# Timebase_shcematics.net
KiCad netlist of a schematic drawn in Altium Designer
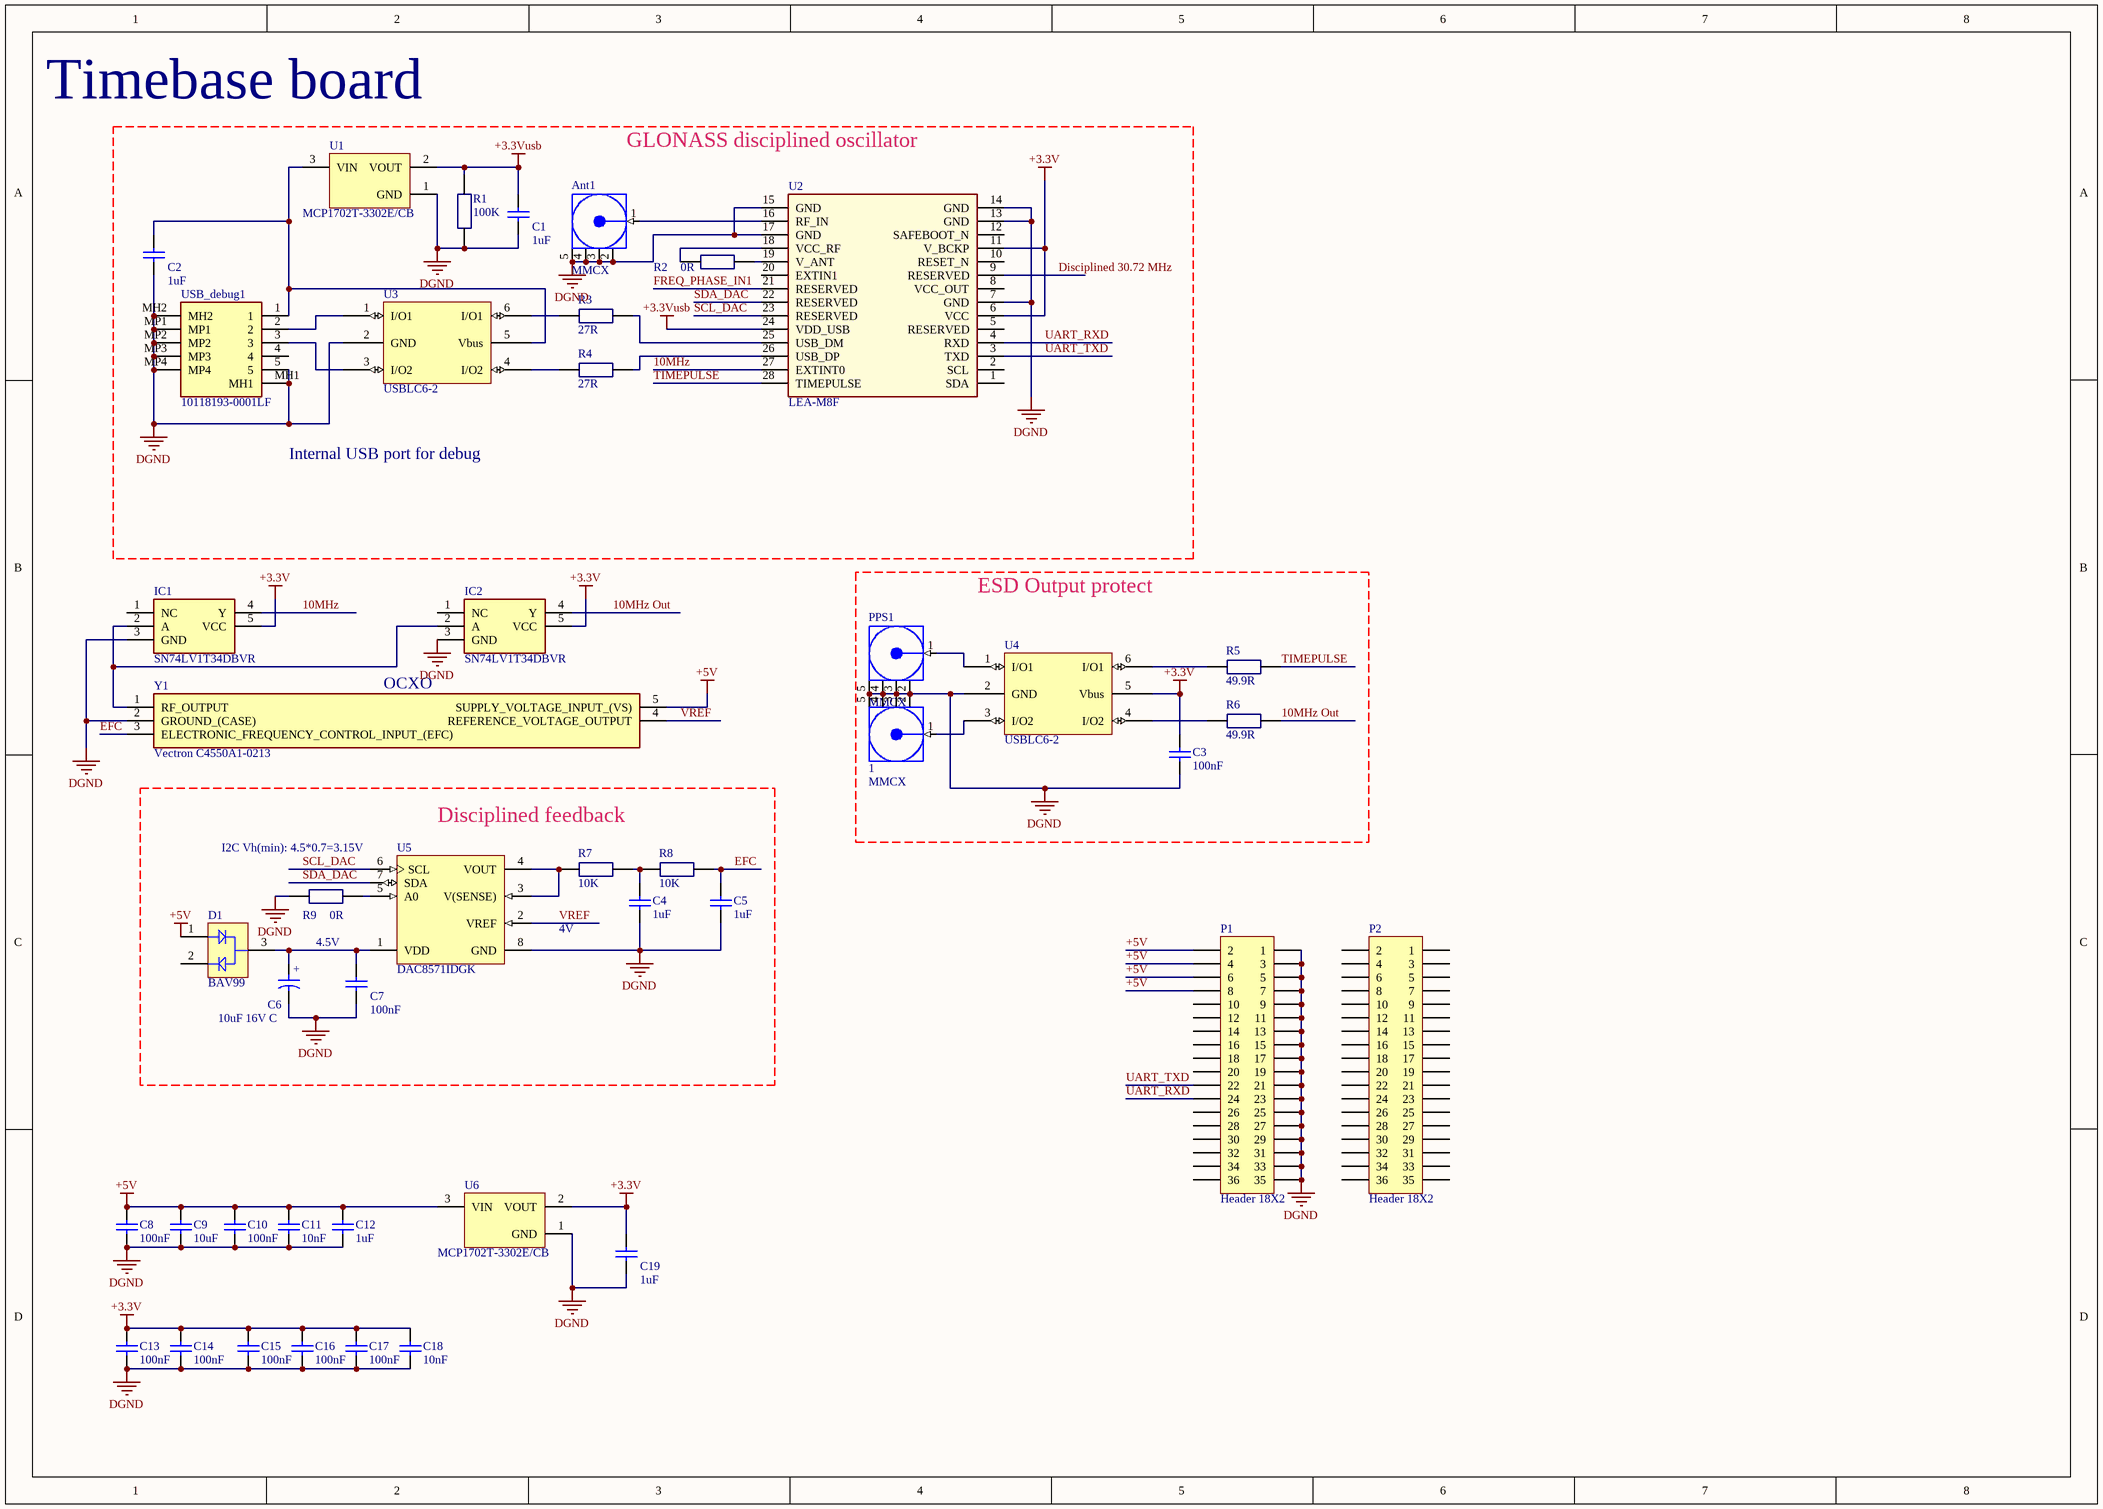
[diagram p0: Timebase_shcematics.SchDoc]

(export (version "E")
  (design (tool "Eeschema 10.0.6"))
  (components
    (comp (ref "1")
      (value "MMCX")
      (footprint "MMCX2.54-V5")
      (description "RF Coaxial PCB Connector, MMCX; Thru-Hole, Vertical Mount Plug,  50 Ohm Impedance")
      (fields (field (name "PUBLISHER") "Altium Limited"))
      (libsource (lib "Miscellaneous Connectors") (part "COAX-M"))
    )
    (comp (ref "Ant1")
      (value "MMCX")
      (footprint "MMCX2.54-V5")
      (description "RF Coaxial PCB Connector, MMCX; Thru-Hole, Vertical Mount Plug,  50 Ohm Impedance")
      (fields (field (name "PUBLISHER") "Altium Limited"))
      (libsource (lib "Miscellaneous Connectors") (part "COAX-M"))
    )
    (comp (ref "C1")
      (value "1uF")
      (footprint "CAP 0603")
      (description "Capacitor (Semiconductor SIM Model)")
      (fields (field (name "PUBLISHER") "Altium Limited"))
      (libsource (lib "Miscellaneous Devices") (part "Cap Semi"))
    )
    (comp (ref "C2")
      (value "1uF")
      (footprint "CAP 0603")
      (description "Capacitor (Semiconductor SIM Model)")
      (fields (field (name "PUBLISHER") "Altium Limited"))
      (libsource (lib "Miscellaneous Devices") (part "Cap Semi"))
    )
    (comp (ref "C3")
      (value "100nF")
      (footprint "CAP 0603")
      (description "Capacitor (Semiconductor SIM Model)")
      (fields (field (name "PUBLISHER") "Altium Limited"))
      (libsource (lib "Miscellaneous Devices") (part "Cap Semi"))
    )
    (comp (ref "C4")
      (value "1uF")
      (footprint "CAP 0603")
      (description "Capacitor (Semiconductor SIM Model)")
      (fields (field (name "PUBLISHER") "Altium Limited"))
      (libsource (lib "Miscellaneous Devices") (part "Cap Semi"))
    )
    (comp (ref "C5")
      (value "1uF")
      (footprint "CAP 0603")
      (description "Capacitor (Semiconductor SIM Model)")
      (fields (field (name "PUBLISHER") "Altium Limited"))
      (libsource (lib "Miscellaneous Devices") (part "Cap Semi"))
    )
    (comp (ref "C6")
      (value "10uF 16V C")
      (footprint "CAPMP6032X280N")
      (description "Polarised capacitor")
      (fields
        (field (name "PART NUMBER") "CTE6032-28_10UF_25V_10%_LESR0500")
        (field (name "VOLTAGE") "25V")
        (field (name "AUTHOR") "CERN DEM JLC")
      )
      (libsource (lib "Capacitors") (part "Capacitor - polarized"))
    )
    (comp (ref "C7")
      (value "100nF")
      (footprint "CAP 0603")
      (description "Capacitor (Semiconductor SIM Model)")
      (fields (field (name "PUBLISHER") "Altium Limited"))
      (libsource (lib "Miscellaneous Devices") (part "Cap Semi"))
    )
    (comp (ref "C8")
      (value "100nF")
      (footprint "CAP 0603")
      (description "Capacitor (Semiconductor SIM Model)")
      (fields (field (name "PUBLISHER") "Altium Limited"))
      (libsource (lib "Miscellaneous Devices") (part "Cap Semi"))
    )
    (comp (ref "C9")
      (value "10uF")
      (footprint "CAP 0603")
      (description "Capacitor (Semiconductor SIM Model)")
      (fields (field (name "PUBLISHER") "Altium Limited"))
      (libsource (lib "Miscellaneous Devices") (part "Cap Semi"))
    )
    (comp (ref "C10")
      (value "100nF")
      (footprint "CAP 0603")
      (description "Capacitor (Semiconductor SIM Model)")
      (fields (field (name "PUBLISHER") "Altium Limited"))
      (libsource (lib "Miscellaneous Devices") (part "Cap Semi"))
    )
    (comp (ref "C11")
      (value "10nF")
      (footprint "CAP 0603")
      (description "Capacitor (Semiconductor SIM Model)")
      (fields (field (name "PUBLISHER") "Altium Limited"))
      (libsource (lib "Miscellaneous Devices") (part "Cap Semi"))
    )
    (comp (ref "C12")
      (value "1uF")
      (footprint "CAP 0603")
      (description "Capacitor (Semiconductor SIM Model)")
      (fields (field (name "PUBLISHER") "Altium Limited"))
      (libsource (lib "Miscellaneous Devices") (part "Cap Semi"))
    )
    (comp (ref "C13")
      (value "100nF")
      (footprint "CAP 0603")
      (description "Capacitor (Semiconductor SIM Model)")
      (fields (field (name "PUBLISHER") "Altium Limited"))
      (libsource (lib "Miscellaneous Devices") (part "Cap Semi"))
    )
    (comp (ref "C14")
      (value "100nF")
      (footprint "CAP 0603")
      (description "Capacitor (Semiconductor SIM Model)")
      (fields (field (name "PUBLISHER") "Altium Limited"))
      (libsource (lib "Miscellaneous Devices") (part "Cap Semi"))
    )
    (comp (ref "C15")
      (value "100nF")
      (footprint "CAP 0603")
      (description "Capacitor (Semiconductor SIM Model)")
      (fields (field (name "PUBLISHER") "Altium Limited"))
      (libsource (lib "Miscellaneous Devices") (part "Cap Semi"))
    )
    (comp (ref "C16")
      (value "100nF")
      (footprint "CAP 0603")
      (description "Capacitor (Semiconductor SIM Model)")
      (fields (field (name "PUBLISHER") "Altium Limited"))
      (libsource (lib "Miscellaneous Devices") (part "Cap Semi"))
    )
    (comp (ref "C17")
      (value "100nF")
      (footprint "CAP 0603")
      (description "Capacitor (Semiconductor SIM Model)")
      (fields (field (name "PUBLISHER") "Altium Limited"))
      (libsource (lib "Miscellaneous Devices") (part "Cap Semi"))
    )
    (comp (ref "C18")
      (value "10nF")
      (footprint "CAP 0603")
      (description "Capacitor (Semiconductor SIM Model)")
      (fields (field (name "PUBLISHER") "Altium Limited"))
      (libsource (lib "Miscellaneous Devices") (part "Cap Semi"))
    )
    (comp (ref "C19")
      (value "1uF")
      (footprint "CAP 0603")
      (description "Capacitor (Semiconductor SIM Model)")
      (fields (field (name "PUBLISHER") "Altium Limited"))
      (libsource (lib "Miscellaneous Devices") (part "Cap Semi"))
    )
    (comp (ref "D1")
      (value "BAV99")
      (footprint "INF-SOT23_N")
      (description "Silicon Switching Diode, SOT23, Reel, Green")
      (fields (field (name "MANUFACTURER") "Infineon"))
      (libsource (lib "Infineon_Transistor_&_Diode") (part "BAV99"))
    )
    (comp (ref "IC1")
      (value "SN74LV1T34DBVR")
      (footprint "SamacSys:SOT95P280X145-5N")
      (description "Integrated Circuit")
      (fields (field (name "MOUSER PART NUMBER") "595-SN74LV1T34DBVR"))
      (libsource (lib "*") (part "SN74LV1T34DBVR"))
    )
    (comp (ref "IC2")
      (value "SN74LV1T34DBVR")
      (footprint "SamacSys:SOT95P280X145-5N")
      (description "Integrated Circuit")
      (fields (field (name "MOUSER PART NUMBER") "595-SN74LV1T34DBVR"))
      (libsource (lib "*") (part "SN74LV1T34DBVR"))
    )
    (comp (ref "P1")
      (value "Header 18X2")
      (footprint "HDR2X18")
      (description "Header, 18-Pin, Dual row")
      (fields (field (name "PUBLISHER") "Altium Limited"))
      (libsource (lib "Miscellaneous Connectors") (part "Header 18X2"))
    )
    (comp (ref "P2")
      (value "Header 18X2")
      (footprint "HDR2X18")
      (description "Header, 18-Pin, Dual row")
      (fields (field (name "PUBLISHER") "Altium Limited"))
      (libsource (lib "Miscellaneous Connectors") (part "Header 18X2"))
    )
    (comp (ref "PPS1")
      (value "MMCX")
      (footprint "MMCX2.54-V5")
      (description "RF Coaxial PCB Connector, MMCX; Thru-Hole, Vertical Mount Plug,  50 Ohm Impedance")
      (fields (field (name "PUBLISHER") "Altium Limited"))
      (libsource (lib "Miscellaneous Connectors") (part "COAX-M"))
    )
    (comp (ref "R1")
      (value "100K")
      (footprint "1608[0603]")
      (libsource (lib "Микрон-3") (part "Resistor 0805"))
    )
    (comp (ref "R2")
      (value "0R")
      (footprint "1608[0603]")
      (libsource (lib "Микрон-3") (part "Resistor 0805"))
    )
    (comp (ref "R3")
      (value "27R")
      (footprint "1608[0603]")
      (libsource (lib "Микрон-3") (part "Resistor 0805"))
    )
    (comp (ref "R4")
      (value "27R")
      (footprint "1608[0603]")
      (libsource (lib "Микрон-3") (part "Resistor 0805"))
    )
    (comp (ref "R5")
      (value "49.9R")
      (footprint "1608[0603]")
      (libsource (lib "Микрон-3") (part "Resistor 0805"))
    )
    (comp (ref "R6")
      (value "49.9R")
      (footprint "1608[0603]")
      (libsource (lib "Микрон-3") (part "Resistor 0805"))
    )
    (comp (ref "R7")
      (value "10K")
      (footprint "1608[0603]")
      (libsource (lib "Микрон-3") (part "Resistor 0805"))
    )
    (comp (ref "R8")
      (value "10K")
      (footprint "1608[0603]")
      (libsource (lib "Микрон-3") (part "Resistor 0805"))
    )
    (comp (ref "R9")
      (value "0R")
      (footprint "1608[0603]")
      (libsource (lib "Микрон-3") (part "Resistor 0805"))
    )
    (comp (ref "U1")
      (value "MCP1702T-3302E/CB")
      (footprint "SOT-23A-CB3_N")
      (description "250 mA Low Quiescent Current LDO Regulator, 3-Pin SOT-23A, Extended Temperature, Tape and Reel")
      (fields (field (name "PUBLISHER") "Altium Limited"))
      (libsource (lib "Microchip Power Mgt Line Regulator") (part "MCP1702T-3302E/CB"))
    )
    (comp (ref "U2")
      (value "LEA-M8F")
      (footprint "LEA")
      (description "u-blox LEA GNSS module")
      (fields (field (name "MANUFACTURER") "u-blox"))
      (libsource (lib "ubloxLib") (part "LEA"))
    )
    (comp (ref "U3") (value "USBLC6-2") (footprint "SOT23-6L") (libsource (lib "Микрон-3") (part "USBLC6-2")))
    (comp (ref "U4") (value "USBLC6-2") (footprint "SOT23-6L") (libsource (lib "Микрон-3") (part "USBLC6-2")))
    (comp (ref "U5")
      (value "DAC8571IDGK")
      (footprint "TI-DGK8_N")
      (fields (field (name "MANUFACTURER") "Texas Instruments"))
      (libsource (lib "TI Data Converters Digital to Analog Converter") (part "DAC8571IDGK"))
    )
    (comp (ref "U6")
      (value "MCP1702T-3302E/CB")
      (footprint "SOT-23A-CB3_N")
      (description "250 mA Low Quiescent Current LDO Regulator, 3-Pin SOT-23A, Extended Temperature, Tape and Reel")
      (fields (field (name "PUBLISHER") "Altium Limited"))
      (libsource (lib "Microchip Power Mgt Line Regulator") (part "MCP1702T-3302E/CB"))
    )
    (comp (ref "USB_debug1")
      (value "10118193-0001LF")
      (footprint "SamacSys:101181930001LF")
      (description "Connector")
      (fields (field (name "MOUSER PART NUMBER") "649-10118193-0001LF"))
      (libsource (lib "*") (part "10118193-0001LF"))
    )
    (comp (ref "Y1")
      (value "Vectron C4550A1-0213")
      (footprint "SamacSys:C4550C508SV120RFSA11128MHZ")
      (description "Crystal or Oscillator")
      (libsource (lib "SamacSys") (part "C4550C508SV120RFSA1112.8MHZ"))
    )
  )
  (nets
    (net (code "1") (name "+3.3V") (class "Default")
      (node (ref "C13") (pin "2") (pinfunction "2_2") (pintype "passive"))
      (node (ref "C14") (pin "2") (pinfunction "2_2") (pintype "passive"))
      (node (ref "C15") (pin "2") (pinfunction "2_2") (pintype "passive"))
      (node (ref "C16") (pin "2") (pinfunction "2_2") (pintype "passive"))
      (node (ref "C17") (pin "2") (pinfunction "2_2") (pintype "passive"))
      (node (ref "C18") (pin "2") (pinfunction "2_2") (pintype "passive"))
      (node (ref "C19") (pin "2") (pinfunction "2_2") (pintype "passive"))
      (node (ref "C3") (pin "2") (pinfunction "2_2") (pintype "passive"))
      (node (ref "IC1") (pin "5") (pinfunction "VCC_5") (pintype "passive"))
      (node (ref "IC2") (pin "5") (pinfunction "VCC_5") (pintype "passive"))
      (node (ref "U2") (pin "11") (pinfunction "V_BCKP_11") (pintype "passive"))
      (node (ref "U2") (pin "6") (pinfunction "VCC_6") (pintype "passive"))
      (node (ref "U4") (pin "5") (pinfunction "Vbus_5") (pintype "power_in"))
      (node (ref "U6") (pin "2") (pinfunction "VOUT_2") (pintype "power_in"))
    )
    (net (code "2") (name "+3.3Vusb") (class "Default")
      (node (ref "C1") (pin "2") (pinfunction "2_2") (pintype "passive"))
      (node (ref "R1") (pin "1") (pinfunction "A_1") (pintype "passive"))
      (node (ref "U1") (pin "2") (pinfunction "VOUT_2") (pintype "power_in"))
      (node (ref "U2") (pin "24") (pinfunction "VDD_USB_24") (pintype "passive"))
    )
    (net (code "3") (name "+5V") (class "Default")
      (node (ref "C10") (pin "2") (pinfunction "2_2") (pintype "passive"))
      (node (ref "C11") (pin "2") (pinfunction "2_2") (pintype "passive"))
      (node (ref "C12") (pin "2") (pinfunction "2_2") (pintype "passive"))
      (node (ref "C8") (pin "2") (pinfunction "2_2") (pintype "passive"))
      (node (ref "C9") (pin "2") (pinfunction "2_2") (pintype "passive"))
      (node (ref "D1") (pin "1") (pinfunction "A1_1") (pintype "passive"))
      (node (ref "P1") (pin "2") (pinfunction "2_2") (pintype "passive"))
      (node (ref "P1") (pin "4") (pinfunction "4_4") (pintype "passive"))
      (node (ref "P1") (pin "6") (pinfunction "6_6") (pintype "passive"))
      (node (ref "P1") (pin "8") (pinfunction "8_8") (pintype "passive"))
      (node (ref "U6") (pin "3") (pinfunction "VIN_3") (pintype "power_in"))
      (node (ref "Y1") (pin "5") (pinfunction "SUPPLY_VOLTAGE_INPUT_(VS)_5") (pintype "passive"))
    )
    (net (code "4") (name "/10MHz") (class "Default")
      (node (ref "IC1") (pin "4") (pinfunction "Y_4") (pintype "passive"))
      (node (ref "U2") (pin "27") (pinfunction "EXTINT0_27") (pintype "passive"))
    )
    (net (code "5") (name "/10MHz Out") (class "Default")
      (node (ref "IC2") (pin "4") (pinfunction "Y_4") (pintype "passive"))
      (node (ref "R6") (pin "1") (pinfunction "A_1") (pintype "passive"))
    )
    (net (code "6") (name "/Disciplined 30.72 MHz") (class "Default")
      (node (ref "U2") (pin "9") (pinfunction "RESERVED_9") (pintype "passive"))
    )
    (net (code "7") (name "/EFC") (class "Default")
      (node (ref "C5") (pin "2") (pinfunction "2_2") (pintype "passive"))
      (node (ref "R8") (pin "1") (pinfunction "A_1") (pintype "passive"))
      (node (ref "Y1") (pin "3") (pinfunction "ELECTRONIC_FREQUENCY_CONTROL_INPUT_(EFC)_3") (pintype "passive"))
    )
    (net (code "8") (name "/FREQ_PHASE_IN1") (class "Default")
      (node (ref "U2") (pin "21") (pinfunction "RESERVED_21") (pintype "passive"))
    )
    (net (code "9") (name "/SCL_DAC") (class "Default")
      (node (ref "U2") (pin "23") (pinfunction "RESERVED_23") (pintype "passive"))
      (node (ref "U5") (pin "6") (pinfunction "SCL_6") (pintype "input"))
    )
    (net (code "10") (name "/SDA_DAC") (class "Default")
      (node (ref "U2") (pin "22") (pinfunction "RESERVED_22") (pintype "passive"))
      (node (ref "U5") (pin "7") (pinfunction "SDA_7") (pintype "bidirectional"))
    )
    (net (code "11") (name "/TIMEPULSE") (class "Default")
      (node (ref "R5") (pin "1") (pinfunction "A_1") (pintype "passive"))
      (node (ref "U2") (pin "28") (pinfunction "TIMEPULSE_28") (pintype "passive"))
    )
    (net (code "12") (name "/UART_RXD") (class "Default")
      (node (ref "P1") (pin "24") (pinfunction "24_24") (pintype "passive"))
      (node (ref "U2") (pin "4") (pinfunction "RXD_4") (pintype "passive"))
    )
    (net (code "13") (name "/UART_TXD") (class "Default")
      (node (ref "P1") (pin "22") (pinfunction "22_22") (pintype "passive"))
      (node (ref "U2") (pin "3") (pinfunction "TXD_3") (pintype "passive"))
    )
    (net (code "14") (name "/VREF") (class "Default")
      (node (ref "U5") (pin "2") (pinfunction "VREF_2") (pintype "input"))
      (node (ref "Y1") (pin "4") (pinfunction "REFERENCE_VOLTAGE_OUTPUT_4") (pintype "passive"))
    )
    (net (code "15") (name "DGND") (class "Default")
      (node (ref "1") (pin "2") (pinfunction "GND_2") (pintype "power_in"))
      (node (ref "1") (pin "3") (pinfunction "GND_3") (pintype "power_in"))
      (node (ref "1") (pin "4") (pinfunction "GND_4") (pintype "power_in"))
      (node (ref "1") (pin "5") (pinfunction "GND_5") (pintype "power_in"))
      (node (ref "Ant1") (pin "2") (pinfunction "GND_2") (pintype "power_in"))
      (node (ref "Ant1") (pin "3") (pinfunction "GND_3") (pintype "power_in"))
      (node (ref "Ant1") (pin "4") (pinfunction "GND_4") (pintype "power_in"))
      (node (ref "Ant1") (pin "5") (pinfunction "GND_5") (pintype "power_in"))
      (node (ref "C1") (pin "1") (pinfunction "1_1") (pintype "passive"))
      (node (ref "C10") (pin "1") (pinfunction "1_1") (pintype "passive"))
      (node (ref "C11") (pin "1") (pinfunction "1_1") (pintype "passive"))
      (node (ref "C12") (pin "1") (pinfunction "1_1") (pintype "passive"))
      (node (ref "C13") (pin "1") (pinfunction "1_1") (pintype "passive"))
      (node (ref "C14") (pin "1") (pinfunction "1_1") (pintype "passive"))
      (node (ref "C15") (pin "1") (pinfunction "1_1") (pintype "passive"))
      (node (ref "C16") (pin "1") (pinfunction "1_1") (pintype "passive"))
      (node (ref "C17") (pin "1") (pinfunction "1_1") (pintype "passive"))
      (node (ref "C18") (pin "1") (pinfunction "1_1") (pintype "passive"))
      (node (ref "C19") (pin "1") (pinfunction "1_1") (pintype "passive"))
      (node (ref "C2") (pin "1") (pinfunction "1_1") (pintype "passive"))
      (node (ref "C3") (pin "1") (pinfunction "1_1") (pintype "passive"))
      (node (ref "C4") (pin "1") (pinfunction "1_1") (pintype "passive"))
      (node (ref "C5") (pin "1") (pinfunction "1_1") (pintype "passive"))
      (node (ref "C6") (pin "2") (pinfunction "2_2") (pintype "passive"))
      (node (ref "C7") (pin "1") (pinfunction "1_1") (pintype "passive"))
      (node (ref "C8") (pin "1") (pinfunction "1_1") (pintype "passive"))
      (node (ref "C9") (pin "1") (pinfunction "1_1") (pintype "passive"))
      (node (ref "IC1") (pin "3") (pinfunction "GND_3") (pintype "passive"))
      (node (ref "IC2") (pin "3") (pinfunction "GND_3") (pintype "passive"))
      (node (ref "P1") (pin "1") (pinfunction "1_1") (pintype "passive"))
      (node (ref "P1") (pin "11") (pinfunction "11_11") (pintype "passive"))
      (node (ref "P1") (pin "13") (pinfunction "13_13") (pintype "passive"))
      (node (ref "P1") (pin "15") (pinfunction "15_15") (pintype "passive"))
      (node (ref "P1") (pin "17") (pinfunction "17_17") (pintype "passive"))
      (node (ref "P1") (pin "19") (pinfunction "19_19") (pintype "passive"))
      (node (ref "P1") (pin "21") (pinfunction "21_21") (pintype "passive"))
      (node (ref "P1") (pin "23") (pinfunction "23_23") (pintype "passive"))
      (node (ref "P1") (pin "25") (pinfunction "25_25") (pintype "passive"))
      (node (ref "P1") (pin "27") (pinfunction "27_27") (pintype "passive"))
      (node (ref "P1") (pin "29") (pinfunction "29_29") (pintype "passive"))
      (node (ref "P1") (pin "3") (pinfunction "3_3") (pintype "passive"))
      (node (ref "P1") (pin "31") (pinfunction "31_31") (pintype "passive"))
      (node (ref "P1") (pin "33") (pinfunction "33_33") (pintype "passive"))
      (node (ref "P1") (pin "35") (pinfunction "35_35") (pintype "passive"))
      (node (ref "P1") (pin "5") (pinfunction "5_5") (pintype "passive"))
      (node (ref "P1") (pin "7") (pinfunction "7_7") (pintype "passive"))
      (node (ref "P1") (pin "9") (pinfunction "9_9") (pintype "passive"))
      (node (ref "PPS1") (pin "2") (pinfunction "GND_2") (pintype "power_in"))
      (node (ref "PPS1") (pin "3") (pinfunction "GND_3") (pintype "power_in"))
      (node (ref "PPS1") (pin "4") (pinfunction "GND_4") (pintype "power_in"))
      (node (ref "PPS1") (pin "5") (pinfunction "GND_5") (pintype "power_in"))
      (node (ref "R1") (pin "2") (pinfunction "2_2") (pintype "passive"))
      (node (ref "R9") (pin "2") (pinfunction "2_2") (pintype "passive"))
      (node (ref "U1") (pin "1") (pinfunction "GND_1") (pintype "power_in"))
      (node (ref "U2") (pin "13") (pinfunction "GND_13") (pintype "passive"))
      (node (ref "U2") (pin "14") (pinfunction "GND_14") (pintype "passive"))
      (node (ref "U2") (pin "15") (pinfunction "GND_15") (pintype "passive"))
      (node (ref "U2") (pin "17") (pinfunction "GND_17") (pintype "passive"))
      (node (ref "U2") (pin "7") (pinfunction "GND_7") (pintype "passive"))
      (node (ref "U3") (pin "2") (pinfunction "GND_2") (pintype "power_in"))
      (node (ref "U4") (pin "2") (pinfunction "GND_2") (pintype "power_in"))
      (node (ref "U5") (pin "8") (pinfunction "GND_8") (pintype "power_in"))
      (node (ref "U6") (pin "1") (pinfunction "GND_1") (pintype "power_in"))
      (node (ref "USB_debug1") (pin "5") (pinfunction "5_5") (pintype "passive"))
      (node (ref "USB_debug1") (pin "MH1") (pinfunction "MH1_MH1") (pintype "passive"))
      (node (ref "USB_debug1") (pin "MH2") (pinfunction "MH2_MH2") (pintype "passive"))
      (node (ref "USB_debug1") (pin "MP1") (pinfunction "MP1_MP1") (pintype "passive"))
      (node (ref "USB_debug1") (pin "MP2") (pinfunction "MP2_MP2") (pintype "passive"))
      (node (ref "USB_debug1") (pin "MP3") (pinfunction "MP3_MP3") (pintype "passive"))
      (node (ref "USB_debug1") (pin "MP4") (pinfunction "MP4_MP4") (pintype "passive"))
      (node (ref "Y1") (pin "2") (pinfunction "GROUND_(CASE)_2") (pintype "passive"))
    )
    (net (code "16") (name "Net-(1-Signal)") (class "Default")
      (node (ref "1") (pin "1") (pinfunction "Signal_1") (pintype "input"))
      (node (ref "U4") (pin "3") (pinfunction "I/O2_3") (pintype "bidirectional"))
    )
    (net (code "17") (name "Net-(Ant1-Signal)") (class "Default")
      (node (ref "Ant1") (pin "1") (pinfunction "Signal_1") (pintype "input"))
      (node (ref "U2") (pin "16") (pinfunction "RF_IN_16") (pintype "passive"))
    )
    (net (code "18") (name "Net-(D1-C)") (class "Default")
      (node (ref "C6") (pin "1") (pinfunction "1_1") (pintype "passive"))
      (node (ref "C7") (pin "2") (pinfunction "2_2") (pintype "passive"))
      (node (ref "D1") (pin "3") (pinfunction "C_3") (pintype "passive"))
      (node (ref "U5") (pin "1") (pinfunction "VDD_1") (pintype "power_in"))
    )
    (net (code "19") (name "Net-(IC1-A)") (class "Default")
      (node (ref "IC1") (pin "2") (pinfunction "A_2") (pintype "passive"))
      (node (ref "IC2") (pin "2") (pinfunction "A_2") (pintype "passive"))
      (node (ref "Y1") (pin "1") (pinfunction "RF_OUTPUT_1") (pintype "passive"))
    )
    (net (code "20") (name "Net-(PPS1-Signal)") (class "Default")
      (node (ref "PPS1") (pin "1") (pinfunction "Signal_1") (pintype "input"))
      (node (ref "U4") (pin "1") (pinfunction "I/O1_1") (pintype "bidirectional"))
    )
    (net (code "21") (name "Net-(R2-A)") (class "Default")
      (node (ref "R2") (pin "1") (pinfunction "A_1") (pintype "passive"))
      (node (ref "U2") (pin "19") (pinfunction "V_ANT_19") (pintype "passive"))
    )
    (net (code "22") (name "Net-(R3-A)") (class "Default")
      (node (ref "R3") (pin "1") (pinfunction "A_1") (pintype "passive"))
      (node (ref "U2") (pin "25") (pinfunction "USB_DM_25") (pintype "passive"))
    )
    (net (code "23") (name "Net-(R3-Pad2)") (class "Default")
      (node (ref "R3") (pin "2") (pinfunction "2_2") (pintype "passive"))
      (node (ref "U3") (pin "6") (pinfunction "I/O1_6") (pintype "bidirectional"))
    )
    (net (code "24") (name "Net-(R4-A)") (class "Default")
      (node (ref "R4") (pin "1") (pinfunction "A_1") (pintype "passive"))
      (node (ref "U2") (pin "26") (pinfunction "USB_DP_26") (pintype "passive"))
    )
    (net (code "25") (name "Net-(R4-Pad2)") (class "Default")
      (node (ref "R4") (pin "2") (pinfunction "2_2") (pintype "passive"))
      (node (ref "U3") (pin "4") (pinfunction "I/O2_4") (pintype "bidirectional"))
    )
    (net (code "26") (name "Net-(R5-Pad2)") (class "Default")
      (node (ref "R5") (pin "2") (pinfunction "2_2") (pintype "passive"))
      (node (ref "U4") (pin "6") (pinfunction "I/O1_6") (pintype "bidirectional"))
    )
    (net (code "27") (name "Net-(R6-Pad2)") (class "Default")
      (node (ref "R6") (pin "2") (pinfunction "2_2") (pintype "passive"))
      (node (ref "U4") (pin "4") (pinfunction "I/O2_4") (pintype "bidirectional"))
    )
    (net (code "28") (name "Net-(R7-A)") (class "Default")
      (node (ref "C4") (pin "2") (pinfunction "2_2") (pintype "passive"))
      (node (ref "R7") (pin "1") (pinfunction "A_1") (pintype "passive"))
      (node (ref "R8") (pin "2") (pinfunction "2_2") (pintype "passive"))
    )
    (net (code "29") (name "Net-(R9-A)") (class "Default")
      (node (ref "R9") (pin "1") (pinfunction "A_1") (pintype "passive"))
      (node (ref "U5") (pin "5") (pinfunction "A0_5") (pintype "input"))
    )
    (net (code "30") (name "Net-(U1-VIN)") (class "Default")
      (node (ref "C2") (pin "2") (pinfunction "2_2") (pintype "passive"))
      (node (ref "U1") (pin "3") (pinfunction "VIN_3") (pintype "power_in"))
      (node (ref "U3") (pin "5") (pinfunction "Vbus_5") (pintype "power_in"))
      (node (ref "USB_debug1") (pin "1") (pinfunction "1_1") (pintype "passive"))
    )
    (net (code "31") (name "Net-(U2-VCC_RF)") (class "Default")
      (node (ref "R2") (pin "2") (pinfunction "2_2") (pintype "passive"))
      (node (ref "U2") (pin "18") (pinfunction "VCC_RF_18") (pintype "passive"))
    )
    (net (code "32") (name "Net-(U3-I{slash}O1-Pad1)") (class "Default")
      (node (ref "U3") (pin "1") (pinfunction "I/O1_1") (pintype "bidirectional"))
      (node (ref "USB_debug1") (pin "2") (pinfunction "2_2") (pintype "passive"))
    )
    (net (code "33") (name "Net-(U3-I{slash}O2-Pad3)") (class "Default")
      (node (ref "U3") (pin "3") (pinfunction "I/O2_3") (pintype "bidirectional"))
      (node (ref "USB_debug1") (pin "3") (pinfunction "3_3") (pintype "passive"))
    )
    (net (code "34") (name "Net-(U5-V(SENSE))") (class "Default")
      (node (ref "R7") (pin "2") (pinfunction "2_2") (pintype "passive"))
      (node (ref "U5") (pin "3") (pinfunction "V(SENSE)_3") (pintype "input"))
      (node (ref "U5") (pin "4") (pinfunction "VOUT_4") (pintype "tri_state"))
    )
    (net (code "35") (name "unconnected-(D1-K2-Pad2)") (class "Default")
      (node (ref "D1") (pin "2") (pinfunction "K2_2") (pintype "passive"))
    )
    (net (code "36") (name "unconnected-(IC1-NC-Pad1)") (class "Default")
      (node (ref "IC1") (pin "1") (pinfunction "NC_1") (pintype "passive"))
    )
    (net (code "37") (name "unconnected-(IC2-NC-Pad1)") (class "Default")
      (node (ref "IC2") (pin "1") (pinfunction "NC_1") (pintype "passive"))
    )
    (net (code "38") (name "unconnected-(P1-Pad10)") (class "Default")
      (node (ref "P1") (pin "10") (pinfunction "10_10") (pintype "passive"))
    )
    (net (code "39") (name "unconnected-(P1-Pad12)") (class "Default")
      (node (ref "P1") (pin "12") (pinfunction "12_12") (pintype "passive"))
    )
    (net (code "40") (name "unconnected-(P1-Pad14)") (class "Default")
      (node (ref "P1") (pin "14") (pinfunction "14_14") (pintype "passive"))
    )
    (net (code "41") (name "unconnected-(P1-Pad16)") (class "Default")
      (node (ref "P1") (pin "16") (pinfunction "16_16") (pintype "passive"))
    )
    (net (code "42") (name "unconnected-(P1-Pad18)") (class "Default")
      (node (ref "P1") (pin "18") (pinfunction "18_18") (pintype "passive"))
    )
    (net (code "43") (name "unconnected-(P1-Pad20)") (class "Default")
      (node (ref "P1") (pin "20") (pinfunction "20_20") (pintype "passive"))
    )
    (net (code "44") (name "unconnected-(P1-Pad26)") (class "Default")
      (node (ref "P1") (pin "26") (pinfunction "26_26") (pintype "passive"))
    )
    (net (code "45") (name "unconnected-(P1-Pad28)") (class "Default")
      (node (ref "P1") (pin "28") (pinfunction "28_28") (pintype "passive"))
    )
    (net (code "46") (name "unconnected-(P1-Pad30)") (class "Default")
      (node (ref "P1") (pin "30") (pinfunction "30_30") (pintype "passive"))
    )
    (net (code "47") (name "unconnected-(P1-Pad32)") (class "Default")
      (node (ref "P1") (pin "32") (pinfunction "32_32") (pintype "passive"))
    )
    (net (code "48") (name "unconnected-(P1-Pad34)") (class "Default")
      (node (ref "P1") (pin "34") (pinfunction "34_34") (pintype "passive"))
    )
    (net (code "49") (name "unconnected-(P1-Pad36)") (class "Default")
      (node (ref "P1") (pin "36") (pinfunction "36_36") (pintype "passive"))
    )
    (net (code "50") (name "unconnected-(P2-Pad1)") (class "Default")
      (node (ref "P2") (pin "1") (pinfunction "1_1") (pintype "passive"))
    )
    (net (code "51") (name "unconnected-(P2-Pad2)") (class "Default")
      (node (ref "P2") (pin "2") (pinfunction "2_2") (pintype "passive"))
    )
    (net (code "52") (name "unconnected-(P2-Pad3)") (class "Default")
      (node (ref "P2") (pin "3") (pinfunction "3_3") (pintype "passive"))
    )
    (net (code "53") (name "unconnected-(P2-Pad4)") (class "Default")
      (node (ref "P2") (pin "4") (pinfunction "4_4") (pintype "passive"))
    )
    (net (code "54") (name "unconnected-(P2-Pad5)") (class "Default")
      (node (ref "P2") (pin "5") (pinfunction "5_5") (pintype "passive"))
    )
    (net (code "55") (name "unconnected-(P2-Pad6)") (class "Default")
      (node (ref "P2") (pin "6") (pinfunction "6_6") (pintype "passive"))
    )
    (net (code "56") (name "unconnected-(P2-Pad7)") (class "Default")
      (node (ref "P2") (pin "7") (pinfunction "7_7") (pintype "passive"))
    )
    (net (code "57") (name "unconnected-(P2-Pad8)") (class "Default")
      (node (ref "P2") (pin "8") (pinfunction "8_8") (pintype "passive"))
    )
    (net (code "58") (name "unconnected-(P2-Pad9)") (class "Default")
      (node (ref "P2") (pin "9") (pinfunction "9_9") (pintype "passive"))
    )
    (net (code "59") (name "unconnected-(P2-Pad10)") (class "Default")
      (node (ref "P2") (pin "10") (pinfunction "10_10") (pintype "passive"))
    )
    (net (code "60") (name "unconnected-(P2-Pad11)") (class "Default")
      (node (ref "P2") (pin "11") (pinfunction "11_11") (pintype "passive"))
    )
    (net (code "61") (name "unconnected-(P2-Pad12)") (class "Default")
      (node (ref "P2") (pin "12") (pinfunction "12_12") (pintype "passive"))
    )
    (net (code "62") (name "unconnected-(P2-Pad13)") (class "Default")
      (node (ref "P2") (pin "13") (pinfunction "13_13") (pintype "passive"))
    )
    (net (code "63") (name "unconnected-(P2-Pad14)") (class "Default")
      (node (ref "P2") (pin "14") (pinfunction "14_14") (pintype "passive"))
    )
    (net (code "64") (name "unconnected-(P2-Pad15)") (class "Default")
      (node (ref "P2") (pin "15") (pinfunction "15_15") (pintype "passive"))
    )
    (net (code "65") (name "unconnected-(P2-Pad16)") (class "Default")
      (node (ref "P2") (pin "16") (pinfunction "16_16") (pintype "passive"))
    )
    (net (code "66") (name "unconnected-(P2-Pad17)") (class "Default")
      (node (ref "P2") (pin "17") (pinfunction "17_17") (pintype "passive"))
    )
    (net (code "67") (name "unconnected-(P2-Pad18)") (class "Default")
      (node (ref "P2") (pin "18") (pinfunction "18_18") (pintype "passive"))
    )
    (net (code "68") (name "unconnected-(P2-Pad19)") (class "Default")
      (node (ref "P2") (pin "19") (pinfunction "19_19") (pintype "passive"))
    )
    (net (code "69") (name "unconnected-(P2-Pad20)") (class "Default")
      (node (ref "P2") (pin "20") (pinfunction "20_20") (pintype "passive"))
    )
    (net (code "70") (name "unconnected-(P2-Pad21)") (class "Default")
      (node (ref "P2") (pin "21") (pinfunction "21_21") (pintype "passive"))
    )
    (net (code "71") (name "unconnected-(P2-Pad22)") (class "Default")
      (node (ref "P2") (pin "22") (pinfunction "22_22") (pintype "passive"))
    )
    (net (code "72") (name "unconnected-(P2-Pad23)") (class "Default")
      (node (ref "P2") (pin "23") (pinfunction "23_23") (pintype "passive"))
    )
    (net (code "73") (name "unconnected-(P2-Pad24)") (class "Default")
      (node (ref "P2") (pin "24") (pinfunction "24_24") (pintype "passive"))
    )
    (net (code "74") (name "unconnected-(P2-Pad25)") (class "Default")
      (node (ref "P2") (pin "25") (pinfunction "25_25") (pintype "passive"))
    )
    (net (code "75") (name "unconnected-(P2-Pad26)") (class "Default")
      (node (ref "P2") (pin "26") (pinfunction "26_26") (pintype "passive"))
    )
    (net (code "76") (name "unconnected-(P2-Pad27)") (class "Default")
      (node (ref "P2") (pin "27") (pinfunction "27_27") (pintype "passive"))
    )
    (net (code "77") (name "unconnected-(P2-Pad28)") (class "Default")
      (node (ref "P2") (pin "28") (pinfunction "28_28") (pintype "passive"))
    )
    (net (code "78") (name "unconnected-(P2-Pad29)") (class "Default")
      (node (ref "P2") (pin "29") (pinfunction "29_29") (pintype "passive"))
    )
    (net (code "79") (name "unconnected-(P2-Pad30)") (class "Default")
      (node (ref "P2") (pin "30") (pinfunction "30_30") (pintype "passive"))
    )
    (net (code "80") (name "unconnected-(P2-Pad31)") (class "Default")
      (node (ref "P2") (pin "31") (pinfunction "31_31") (pintype "passive"))
    )
    (net (code "81") (name "unconnected-(P2-Pad32)") (class "Default")
      (node (ref "P2") (pin "32") (pinfunction "32_32") (pintype "passive"))
    )
    (net (code "82") (name "unconnected-(P2-Pad33)") (class "Default")
      (node (ref "P2") (pin "33") (pinfunction "33_33") (pintype "passive"))
    )
    (net (code "83") (name "unconnected-(P2-Pad34)") (class "Default")
      (node (ref "P2") (pin "34") (pinfunction "34_34") (pintype "passive"))
    )
    (net (code "84") (name "unconnected-(P2-Pad35)") (class "Default")
      (node (ref "P2") (pin "35") (pinfunction "35_35") (pintype "passive"))
    )
    (net (code "85") (name "unconnected-(P2-Pad36)") (class "Default")
      (node (ref "P2") (pin "36") (pinfunction "36_36") (pintype "passive"))
    )
    (net (code "86") (name "unconnected-(U2-EXTIN1-Pad20)") (class "Default")
      (node (ref "U2") (pin "20") (pinfunction "EXTIN1_20") (pintype "passive"))
    )
    (net (code "87") (name "unconnected-(U2-RESERVED-Pad5)") (class "Default")
      (node (ref "U2") (pin "5") (pinfunction "RESERVED_5") (pintype "passive"))
    )
    (net (code "88") (name "unconnected-(U2-RESET_N-Pad10)") (class "Default")
      (node (ref "U2") (pin "10") (pinfunction "RESET_N_10") (pintype "passive"))
    )
    (net (code "89") (name "unconnected-(U2-SAFEBOOT_N-Pad12)") (class "Default")
      (node (ref "U2") (pin "12") (pinfunction "SAFEBOOT_N_12") (pintype "passive"))
    )
    (net (code "90") (name "unconnected-(U2-SCL-Pad2)") (class "Default")
      (node (ref "U2") (pin "2") (pinfunction "SCL_2") (pintype "passive"))
    )
    (net (code "91") (name "unconnected-(U2-SDA-Pad1)") (class "Default")
      (node (ref "U2") (pin "1") (pinfunction "SDA_1") (pintype "passive"))
    )
    (net (code "92") (name "unconnected-(U2-VCC_OUT-Pad8)") (class "Default")
      (node (ref "U2") (pin "8") (pinfunction "VCC_OUT_8") (pintype "passive"))
    )
    (net (code "93") (name "unconnected-(USB_debug1-Pad4)") (class "Default")
      (node (ref "USB_debug1") (pin "4") (pinfunction "4_4") (pintype "passive"))
    )
  )
)
